# mother_card_07.net
KiCad netlist of a schematic drawn in EAGLE
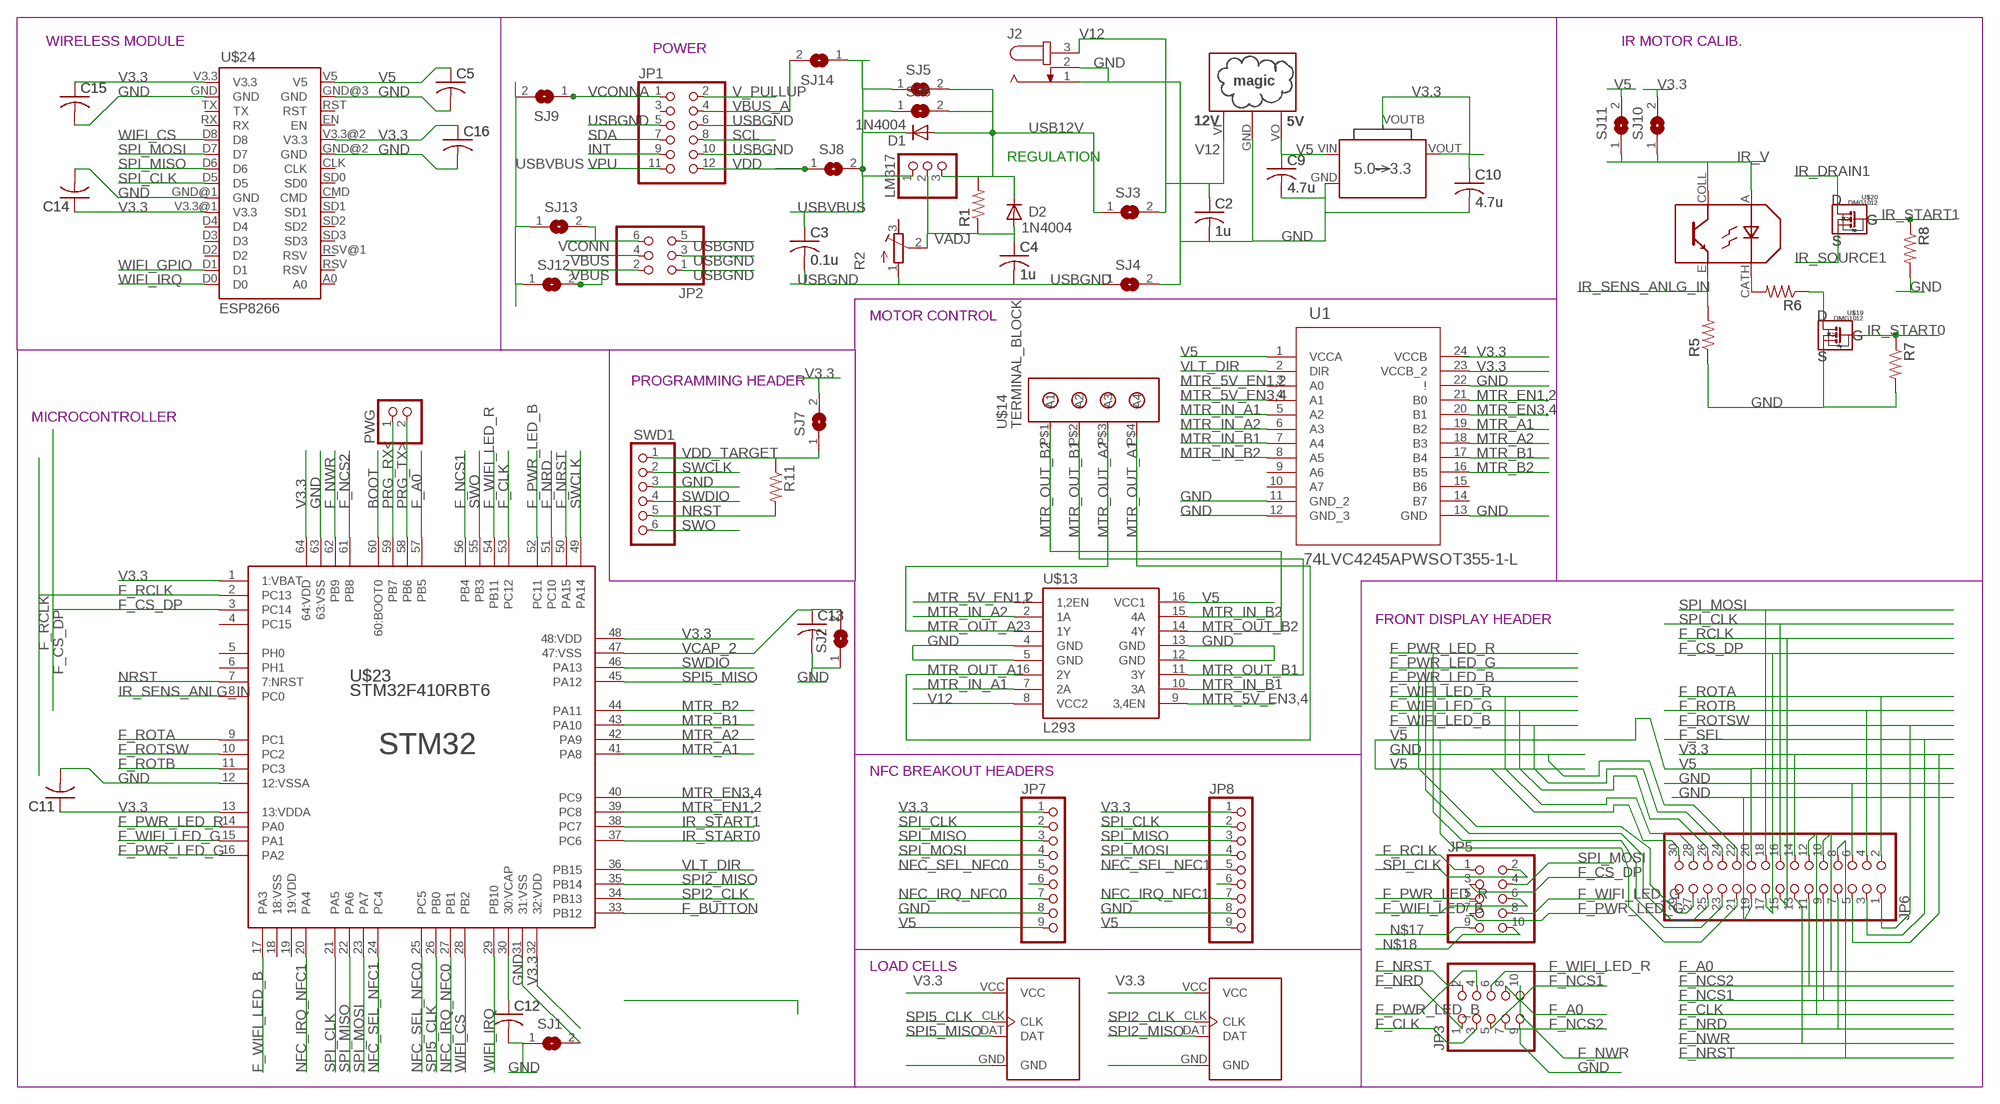
[diagram p0: schematic, sheet 1]

(export (version "E")
  (design (tool "Eeschema 10.0.6"))
  (components
    (comp (ref "C2")
      (value "1u")
      (footprint "eagle-import:C0805")
      (libsource (lib "eagle-import") (part "C-USC0805"))
    )
    (comp (ref "C3")
      (value "0.1u")
      (footprint "eagle-import:C0805")
      (libsource (lib "eagle-import") (part "C-USC0805"))
    )
    (comp (ref "C4")
      (value "1u")
      (footprint "eagle-import:C0805")
      (libsource (lib "eagle-import") (part "C-USC0805"))
    )
    (comp (ref "C5")
      (value "C-USC0805")
      (footprint "eagle-import:C0805")
      (libsource (lib "eagle-import") (part "C-USC0805"))
    )
    (comp (ref "C9")
      (value "4.7u")
      (footprint "eagle-import:C0805")
      (libsource (lib "eagle-import") (part "C-USC0805"))
    )
    (comp (ref "C10")
      (value "4.7u")
      (footprint "eagle-import:C0805")
      (libsource (lib "eagle-import") (part "C-USC0805"))
    )
    (comp (ref "C11")
      (value "C-USC0805")
      (footprint "eagle-import:C0805")
      (libsource (lib "eagle-import") (part "C-USC0805"))
    )
    (comp (ref "C12")
      (value "C-USC0805")
      (footprint "eagle-import:C0805")
      (libsource (lib "eagle-import") (part "C-USC0805"))
    )
    (comp (ref "C13")
      (value "C-USC0805")
      (footprint "eagle-import:C0805")
      (libsource (lib "eagle-import") (part "C-USC0805"))
    )
    (comp (ref "C14")
      (value "C-USC0805")
      (footprint "eagle-import:C0805")
      (libsource (lib "eagle-import") (part "C-USC0805"))
    )
    (comp (ref "C15")
      (value "C-USC0805")
      (footprint "eagle-import:C0805")
      (libsource (lib "eagle-import") (part "C-USC0805"))
    )
    (comp (ref "C16")
      (value "C-USC0805")
      (footprint "eagle-import:C0805")
      (libsource (lib "eagle-import") (part "C-USC0805"))
    )
    (comp (ref "D1")
      (value "1N4004")
      (footprint "eagle-import:DO41-10")
      (libsource (lib "eagle-import") (part "1N4004"))
    )
    (comp (ref "D2")
      (value "1N4004")
      (footprint "eagle-import:DO41-10")
      (libsource (lib "eagle-import") (part "1N4004"))
    )
    (comp (ref "J2")
      (value "JACK-PLUG0")
      (footprint "eagle-import:SPC4077")
      (libsource (lib "eagle-import") (part "JACK-PLUG0"))
    )
    (comp (ref "JP1")
      (value "PINHD-2X6")
      (footprint "eagle-import:2X06")
      (libsource (lib "eagle-import") (part "PINHD-2X6"))
    )
    (comp (ref "JP2")
      (value "PINHD-2X3")
      (footprint "eagle-import:2X03")
      (libsource (lib "eagle-import") (part "PINHD-2X3"))
    )
    (comp (ref "JP3")
      (value "PINHD-2X5")
      (footprint "eagle-import:2X05")
      (libsource (lib "eagle-import") (part "PINHD-2X5"))
    )
    (comp (ref "JP5")
      (value "PINHD-2X5")
      (footprint "eagle-import:2X05")
      (libsource (lib "eagle-import") (part "PINHD-2X5"))
    )
    (comp (ref "JP6")
      (value "PINHD-2X15/SOCK")
      (footprint "eagle-import:2X15_SOCK")
      (libsource (lib "eagle-import") (part "PINHD-2X15/SOCK"))
    )
    (comp (ref "JP7")
      (value "PINHD-1X9/90")
      (footprint "eagle-import:1X09_90")
      (libsource (lib "eagle-import") (part "PINHD-1X9/90"))
    )
    (comp (ref "JP8")
      (value "PINHD-1X9/90")
      (footprint "eagle-import:1X09_90")
      (libsource (lib "eagle-import") (part "PINHD-1X9/90"))
    )
    (comp (ref "LM317")
      (value "PINHD-1X3")
      (footprint "eagle-import:1X03")
      (libsource (lib "eagle-import") (part "PINHD-1X3"))
    )
    (comp (ref "PWG")
      (value "PINHD-1X2")
      (footprint "eagle-import:1X02")
      (libsource (lib "eagle-import") (part "PINHD-1X2"))
    )
    (comp (ref "R1")
      (value "R-US_R0805")
      (footprint "eagle-import:R0805")
      (libsource (lib "eagle-import") (part "seniorDesign_R-US_R0805"))
    )
    (comp (ref "R2")
      (value "R-TRIMM64W")
      (footprint "eagle-import:RTRIM64W")
      (libsource (lib "eagle-import") (part "R-TRIMM64W"))
    )
    (comp (ref "R5")
      (value "R-US_R0805")
      (footprint "eagle-import:R0805")
      (libsource (lib "eagle-import") (part "seniorDesign_R-US_R0805"))
    )
    (comp (ref "R6")
      (value "R-US_R0805")
      (footprint "eagle-import:R0805")
      (libsource (lib "eagle-import") (part "seniorDesign_R-US_R0805"))
    )
    (comp (ref "R7")
      (value "R-US_R0805")
      (footprint "eagle-import:R0805")
      (libsource (lib "eagle-import") (part "seniorDesign_R-US_R0805"))
    )
    (comp (ref "R8")
      (value "R-US_R0805")
      (footprint "eagle-import:R0805")
      (libsource (lib "eagle-import") (part "seniorDesign_R-US_R0805"))
    )
    (comp (ref "R11")
      (value "R-US_R0805")
      (footprint "eagle-import:R0805")
      (libsource (lib "eagle-import") (part "R-US_R0805"))
    )
    (comp (ref "SJ1") (value "SJ") (footprint "eagle-import:SJ") (libsource (lib "eagle-import") (part "SJ")))
    (comp (ref "SJ2") (value "SJ") (footprint "eagle-import:SJ") (libsource (lib "eagle-import") (part "SJ")))
    (comp (ref "SJ3") (value "SJ") (footprint "eagle-import:SJ") (libsource (lib "eagle-import") (part "SJ")))
    (comp (ref "SJ4") (value "SJ") (footprint "eagle-import:SJ") (libsource (lib "eagle-import") (part "SJ")))
    (comp (ref "SJ5") (value "SJ") (footprint "eagle-import:SJ") (libsource (lib "eagle-import") (part "SJ")))
    (comp (ref "SJ6") (value "SJ") (footprint "eagle-import:SJ") (libsource (lib "eagle-import") (part "SJ")))
    (comp (ref "SJ7") (value "SJ") (footprint "eagle-import:SJ") (libsource (lib "eagle-import") (part "SJ")))
    (comp (ref "SJ8") (value "SJ") (footprint "eagle-import:SJ") (libsource (lib "eagle-import") (part "SJ")))
    (comp (ref "SJ9") (value "SJ") (footprint "eagle-import:SJ") (libsource (lib "eagle-import") (part "SJ")))
    (comp (ref "SJ10")
      (value "SJ")
      (footprint "eagle-import:SJ")
      (libsource (lib "eagle-import") (part "SJ"))
    )
    (comp (ref "SJ11")
      (value "SJ")
      (footprint "eagle-import:SJ")
      (libsource (lib "eagle-import") (part "SJ"))
    )
    (comp (ref "SJ12")
      (value "SJ")
      (footprint "eagle-import:SJ")
      (libsource (lib "eagle-import") (part "SJ"))
    )
    (comp (ref "SJ13")
      (value "SJ")
      (footprint "eagle-import:SJ")
      (libsource (lib "eagle-import") (part "SJ"))
    )
    (comp (ref "SJ14")
      (value "SJ")
      (footprint "eagle-import:SJ")
      (libsource (lib "eagle-import") (part "SJ"))
    )
    (comp (ref "SWD1")
      (value "PINHD-1X6")
      (footprint "eagle-import:1X06")
      (libsource (lib "eagle-import") (part "PINHD-1X6"))
    )
    (comp (ref "U$13")
      (value "L293")
      (footprint "eagle-import:DIL16")
      (libsource (lib "eagle-import") (part "L293"))
    )
    (comp (ref "U$14")
      (value "TERMINAL_BLOCK")
      (footprint "eagle-import:1X4_BLOCK")
      (libsource (lib "eagle-import") (part "TERMINAL_BLOCK"))
    )
    (comp (ref "U$15")
      (value "AP2114H")
      (footprint "eagle-import:AP2114H")
      (libsource (lib "eagle-import") (part "AP2114H"))
    )
    (comp (ref "U$16")
      (value "OKI-78SR-W36")
      (footprint "eagle-import:SIP3")
      (libsource (lib "eagle-import") (part "OKI-78SR-W36"))
    )
    (comp (ref "U$18")
      (value "TCRT5000")
      (footprint "eagle-import:TCRT5000")
      (libsource (lib "eagle-import") (part "TCRT5000"))
    )
    (comp (ref "U$19")
      (value "DMG1012")
      (footprint "eagle-import:SOT323")
      (libsource (lib "eagle-import") (part "DMG1012"))
    )
    (comp (ref "U$20")
      (value "DMG1012")
      (footprint "eagle-import:SOT323")
      (libsource (lib "eagle-import") (part "DMG1012"))
    )
    (comp (ref "U$21")
      (value "HX711")
      (footprint "eagle-import:HX711")
      (libsource (lib "eagle-import") (part "HX711"))
    )
    (comp (ref "U$22")
      (value "HX711")
      (footprint "eagle-import:HX711")
      (libsource (lib "eagle-import") (part "HX711"))
    )
    (comp (ref "U$23")
      (value "STM32F410RBT6")
      (footprint "eagle-import:QFP50P1200X1200X160-64N")
      (libsource (lib "eagle-import") (part "STM32F410RBT6"))
    )
    (comp (ref "U$24")
      (value "ESP8266")
      (footprint "eagle-import:ESP8266")
      (libsource (lib "eagle-import") (part "ESP8266"))
    )
    (comp (ref "U1")
      (value "74LVC4245APWSOT355-1-L")
      (footprint "eagle-import:SOT355-1-L")
      (fields (field (name "MANUFACTURER_PART_NUMBER") "74LVC4245APW"))
      (libsource (lib "eagle-import") (part "74LVC4245APWSOT355-1-L"))
    )
  )
  (nets
    (net (code "1") (name "/BOOT") (class "Default")
      (node (ref "U$23") (pin "60") (pinfunction "60:BOOT0_60") (pintype "bidirectional"))
    )
    (net (code "2") (name "/F_A0") (class "Default")
      (node (ref "JP3") (pin "8") (pinfunction "8_8") (pintype "passive"))
      (node (ref "JP6") (pin "10") (pinfunction "10_10") (pintype "passive"))
      (node (ref "U$23") (pin "57") (pinfunction "PB5_57") (pintype "bidirectional"))
    )
    (net (code "3") (name "/F_BUTTON") (class "Default")
      (node (ref "U$23") (pin "33") (pinfunction "PB12_33") (pintype "bidirectional"))
    )
    (net (code "4") (name "/F_CLK") (class "Default")
      (node (ref "JP3") (pin "3") (pinfunction "3_3") (pintype "passive"))
      (node (ref "JP6") (pin "12") (pinfunction "12_12") (pintype "passive"))
      (node (ref "U$23") (pin "53") (pinfunction "PC12_53") (pintype "bidirectional"))
    )
    (net (code "5") (name "/F_CS_DP") (class "Default")
      (node (ref "JP5") (pin "3") (pinfunction "3_3") (pintype "passive"))
      (node (ref "JP6") (pin "17") (pinfunction "17_17") (pintype "passive"))
      (node (ref "U$23") (pin "3") (pinfunction "PC14_3") (pintype "bidirectional"))
    )
    (net (code "6") (name "/F_NCS1") (class "Default")
      (node (ref "JP3") (pin "5") (pinfunction "5_5") (pintype "passive"))
      (node (ref "JP6") (pin "9") (pinfunction "9_9") (pintype "passive"))
      (node (ref "U$23") (pin "56") (pinfunction "PB4_56") (pintype "bidirectional"))
    )
    (net (code "7") (name "/F_NCS2") (class "Default")
      (node (ref "JP3") (pin "7") (pinfunction "7_7") (pintype "passive"))
      (node (ref "JP6") (pin "11") (pinfunction "11_11") (pintype "passive"))
      (node (ref "U$23") (pin "61") (pinfunction "PB8_61") (pintype "bidirectional"))
    )
    (net (code "8") (name "/F_NRD") (class "Default")
      (node (ref "JP3") (pin "1") (pinfunction "1_1") (pintype "passive"))
      (node (ref "JP6") (pin "7") (pinfunction "7_7") (pintype "passive"))
      (node (ref "U$23") (pin "51") (pinfunction "PC10_51") (pintype "bidirectional"))
    )
    (net (code "9") (name "/F_NRST") (class "Default")
      (node (ref "JP3") (pin "2") (pinfunction "2_2") (pintype "passive"))
      (node (ref "JP6") (pin "8") (pinfunction "8_8") (pintype "passive"))
      (node (ref "U$23") (pin "50") (pinfunction "PA15_50") (pintype "bidirectional"))
    )
    (net (code "10") (name "/F_NWR") (class "Default")
      (node (ref "JP3") (pin "10") (pinfunction "10_10") (pintype "passive"))
      (node (ref "JP6") (pin "13") (pinfunction "13_13") (pintype "passive"))
      (node (ref "U$23") (pin "62") (pinfunction "PB9_62") (pintype "bidirectional"))
    )
    (net (code "11") (name "/F_PWR_LED_B") (class "Default")
      (node (ref "JP3") (pin "4") (pinfunction "4_4") (pintype "passive"))
      (node (ref "JP6") (pin "27") (pinfunction "27_27") (pintype "passive"))
      (node (ref "U$23") (pin "52") (pinfunction "PC11_52") (pintype "bidirectional"))
    )
    (net (code "12") (name "/F_PWR_LED_G") (class "Default")
      (node (ref "JP5") (pin "7") (pinfunction "7_7") (pintype "passive"))
      (node (ref "JP6") (pin "25") (pinfunction "25_25") (pintype "passive"))
      (node (ref "U$23") (pin "16") (pinfunction "PA2_16") (pintype "bidirectional"))
    )
    (net (code "13") (name "/F_PWR_LED_R") (class "Default")
      (node (ref "JP5") (pin "5") (pinfunction "5_5") (pintype "passive"))
      (node (ref "JP6") (pin "23") (pinfunction "23_23") (pintype "passive"))
      (node (ref "U$23") (pin "14") (pinfunction "PA0_14") (pintype "bidirectional"))
    )
    (net (code "14") (name "/F_RCLK") (class "Default")
      (node (ref "JP5") (pin "1") (pinfunction "1_1") (pintype "passive"))
      (node (ref "JP6") (pin "15") (pinfunction "15_15") (pintype "passive"))
      (node (ref "U$23") (pin "2") (pinfunction "PC13_2") (pintype "bidirectional"))
    )
    (net (code "15") (name "/F_ROTA") (class "Default")
      (node (ref "JP6") (pin "2") (pinfunction "2_2") (pintype "passive"))
      (node (ref "U$23") (pin "9") (pinfunction "PC1_9") (pintype "bidirectional"))
    )
    (net (code "16") (name "/F_ROTB") (class "Default")
      (node (ref "JP6") (pin "4") (pinfunction "4_4") (pintype "passive"))
      (node (ref "U$23") (pin "11") (pinfunction "PC3_11") (pintype "bidirectional"))
    )
    (net (code "17") (name "/F_ROTSW") (class "Default")
      (node (ref "JP6") (pin "1") (pinfunction "1_1") (pintype "passive"))
      (node (ref "U$23") (pin "10") (pinfunction "PC2_10") (pintype "bidirectional"))
    )
    (net (code "18") (name "/F_SEL") (class "Default")
      (node (ref "JP6") (pin "3") (pinfunction "3_3") (pintype "passive"))
    )
    (net (code "19") (name "/F_WIFI_LED_B") (class "Default")
      (node (ref "JP5") (pin "6") (pinfunction "6_6") (pintype "passive"))
      (node (ref "JP6") (pin "24") (pinfunction "24_24") (pintype "passive"))
      (node (ref "U$23") (pin "17") (pinfunction "PA3_17") (pintype "bidirectional"))
    )
    (net (code "20") (name "/F_WIFI_LED_G") (class "Default")
      (node (ref "JP5") (pin "8") (pinfunction "8_8") (pintype "passive"))
      (node (ref "JP6") (pin "26") (pinfunction "26_26") (pintype "passive"))
      (node (ref "U$23") (pin "15") (pinfunction "PA1_15") (pintype "bidirectional"))
    )
    (net (code "21") (name "/F_WIFI_LED_R") (class "Default")
      (node (ref "JP3") (pin "6") (pinfunction "6_6") (pintype "passive"))
      (node (ref "JP6") (pin "28") (pinfunction "28_28") (pintype "passive"))
      (node (ref "U$23") (pin "54") (pinfunction "PB11_54") (pintype "bidirectional"))
    )
    (net (code "22") (name "/GND") (class "Default")
      (node (ref "C10") (pin "2") (pinfunction "2_2") (pintype "passive"))
      (node (ref "C11") (pin "2") (pinfunction "2_2") (pintype "passive"))
      (node (ref "C12") (pin "2") (pinfunction "2_2") (pintype "passive"))
      (node (ref "C13") (pin "2") (pinfunction "2_2") (pintype "passive"))
      (node (ref "C14") (pin "2") (pinfunction "2_2") (pintype "passive"))
      (node (ref "C15") (pin "2") (pinfunction "2_2") (pintype "passive"))
      (node (ref "C16") (pin "2") (pinfunction "2_2") (pintype "passive"))
      (node (ref "C2") (pin "2") (pinfunction "2_2") (pintype "passive"))
      (node (ref "C5") (pin "2") (pinfunction "2_2") (pintype "passive"))
      (node (ref "C9") (pin "2") (pinfunction "2_2") (pintype "passive"))
      (node (ref "J2") (pin "1") (pinfunction "1_1") (pintype "passive"))
      (node (ref "J2") (pin "2") (pinfunction "2_2") (pintype "passive"))
      (node (ref "JP3") (pin "9") (pinfunction "9_9") (pintype "passive"))
      (node (ref "JP6") (pin "19") (pinfunction "19_19") (pintype "passive"))
      (node (ref "JP6") (pin "22") (pinfunction "22_22") (pintype "passive"))
      (node (ref "JP6") (pin "6") (pinfunction "6_6") (pintype "passive"))
      (node (ref "JP7") (pin "8") (pinfunction "8_8") (pintype "passive"))
      (node (ref "JP8") (pin "8") (pinfunction "8_8") (pintype "passive"))
      (node (ref "R5") (pin "1") (pinfunction "1_1") (pintype "passive"))
      (node (ref "R7") (pin "2") (pinfunction "2_2") (pintype "passive"))
      (node (ref "R8") (pin "2") (pinfunction "2_2") (pintype "passive"))
      (node (ref "SJ1") (pin "1") (pinfunction "1_1") (pintype "passive"))
      (node (ref "SJ1") (pin "2") (pinfunction "2_2") (pintype "passive"))
      (node (ref "SJ2") (pin "1") (pinfunction "1_1") (pintype "passive"))
      (node (ref "SJ4") (pin "2") (pinfunction "2_2") (pintype "passive"))
      (node (ref "SWD1") (pin "3") (pinfunction "3_3") (pintype "passive"))
      (node (ref "U$13") (pin "12") (pinfunction "GND_12") (pintype "bidirectional"))
      (node (ref "U$13") (pin "13") (pinfunction "GND_13") (pintype "bidirectional"))
      (node (ref "U$13") (pin "4") (pinfunction "GND_4") (pintype "bidirectional"))
      (node (ref "U$13") (pin "5") (pinfunction "GND_5") (pintype "bidirectional"))
      (node (ref "U$15") (pin "GND") (pinfunction "GND_GND") (pintype "power_in"))
      (node (ref "U$16") (pin "GND") (pinfunction "P$2_GND") (pintype "power_in"))
      (node (ref "U$19") (pin "S") (pinfunction "S_S") (pintype "bidirectional"))
      (node (ref "U$21") (pin "GND") (pinfunction "GND_GND") (pintype "power_in"))
      (node (ref "U$22") (pin "GND") (pinfunction "GND_GND") (pintype "power_in"))
      (node (ref "U$23") (pin "12") (pinfunction "12:VSSA_12") (pintype "bidirectional"))
      (node (ref "U$23") (pin "31") (pinfunction "31:VSS_31") (pintype "bidirectional"))
      (node (ref "U$23") (pin "63") (pinfunction "63:VSS_63") (pintype "bidirectional"))
      (node (ref "U$24") (pin "GND") (pinfunction "GND_GND") (pintype "bidirectional"))
      (node (ref "U$24") (pin "GND@1") (pinfunction "GND_GND@1") (pintype "bidirectional"))
      (node (ref "U$24") (pin "GND@2") (pinfunction "GND_GND@2") (pintype "bidirectional"))
      (node (ref "U$24") (pin "GND@3") (pinfunction "GND_GND@3") (pintype "bidirectional"))
      (node (ref "U1") (pin "11") (pinfunction "GND_2_11") (pintype "power_in"))
      (node (ref "U1") (pin "12") (pinfunction "GND_3_12") (pintype "power_in"))
      (node (ref "U1") (pin "13") (pinfunction "GND_13") (pintype "power_in"))
      (node (ref "U1") (pin "22") (pinfunction "~_22") (pintype "input"))
    )
    (net (code "23") (name "/INT") (class "Default")
      (node (ref "JP1") (pin "9") (pinfunction "9_9") (pintype "passive"))
    )
    (net (code "24") (name "/IR_DRAIN1") (class "Default")
      (node (ref "U$20") (pin "D") (pinfunction "D_D") (pintype "bidirectional"))
    )
    (net (code "25") (name "/IR_SENS_ANLG_IN") (class "Default")
      (node (ref "R5") (pin "2") (pinfunction "2_2") (pintype "passive"))
      (node (ref "U$18") (pin "E") (pinfunction "E_E") (pintype "bidirectional"))
      (node (ref "U$23") (pin "8") (pinfunction "PC0_8") (pintype "bidirectional"))
    )
    (net (code "26") (name "/IR_SOURCE1") (class "Default")
      (node (ref "U$20") (pin "S") (pinfunction "S_S") (pintype "bidirectional"))
    )
    (net (code "27") (name "/IR_START0") (class "Default")
      (node (ref "R7") (pin "1") (pinfunction "1_1") (pintype "passive"))
      (node (ref "U$19") (pin "G") (pinfunction "G_G") (pintype "bidirectional"))
      (node (ref "U$23") (pin "37") (pinfunction "PC6_37") (pintype "bidirectional"))
    )
    (net (code "28") (name "/IR_START1") (class "Default")
      (node (ref "R8") (pin "1") (pinfunction "1_1") (pintype "passive"))
      (node (ref "U$20") (pin "G") (pinfunction "G_G") (pintype "bidirectional"))
      (node (ref "U$23") (pin "38") (pinfunction "PC7_38") (pintype "bidirectional"))
    )
    (net (code "29") (name "/IR_V") (class "Default")
      (node (ref "SJ10") (pin "1") (pinfunction "1_1") (pintype "passive"))
      (node (ref "SJ11") (pin "1") (pinfunction "1_1") (pintype "passive"))
      (node (ref "U$18") (pin "A") (pinfunction "A_A") (pintype "bidirectional"))
      (node (ref "U$18") (pin "COLL") (pinfunction "COLL_COLL") (pintype "bidirectional"))
    )
    (net (code "30") (name "/MTR_5V_EN1,2") (class "Default")
      (node (ref "U$13") (pin "1") (pinfunction "1,2EN_1") (pintype "bidirectional"))
      (node (ref "U1") (pin "3") (pinfunction "A0_3") (pintype "bidirectional"))
    )
    (net (code "31") (name "/MTR_5V_EN3,4") (class "Default")
      (node (ref "U$13") (pin "9") (pinfunction "3,4EN_9") (pintype "bidirectional"))
      (node (ref "U1") (pin "4") (pinfunction "A1_4") (pintype "bidirectional"))
    )
    (net (code "32") (name "/MTR_A1") (class "Default")
      (node (ref "U$23") (pin "41") (pinfunction "PA8_41") (pintype "bidirectional"))
      (node (ref "U1") (pin "19") (pinfunction "B2_19") (pintype "bidirectional"))
    )
    (net (code "33") (name "/MTR_A2") (class "Default")
      (node (ref "U$23") (pin "42") (pinfunction "PA9_42") (pintype "bidirectional"))
      (node (ref "U1") (pin "18") (pinfunction "B3_18") (pintype "bidirectional"))
    )
    (net (code "34") (name "/MTR_B1") (class "Default")
      (node (ref "U$23") (pin "43") (pinfunction "PA10_43") (pintype "bidirectional"))
      (node (ref "U1") (pin "17") (pinfunction "B4_17") (pintype "bidirectional"))
    )
    (net (code "35") (name "/MTR_B2") (class "Default")
      (node (ref "U$23") (pin "44") (pinfunction "PA11_44") (pintype "bidirectional"))
      (node (ref "U1") (pin "16") (pinfunction "B5_16") (pintype "bidirectional"))
    )
    (net (code "36") (name "/MTR_EN1,2") (class "Default")
      (node (ref "U$23") (pin "39") (pinfunction "PC8_39") (pintype "bidirectional"))
      (node (ref "U1") (pin "21") (pinfunction "B0_21") (pintype "bidirectional"))
    )
    (net (code "37") (name "/MTR_EN3,4") (class "Default")
      (node (ref "U$23") (pin "40") (pinfunction "PC9_40") (pintype "bidirectional"))
      (node (ref "U1") (pin "20") (pinfunction "B1_20") (pintype "bidirectional"))
    )
    (net (code "38") (name "/MTR_IN_A1") (class "Default")
      (node (ref "U$13") (pin "7") (pinfunction "2A_7") (pintype "bidirectional"))
      (node (ref "U1") (pin "5") (pinfunction "A2_5") (pintype "bidirectional"))
    )
    (net (code "39") (name "/MTR_IN_A2") (class "Default")
      (node (ref "U$13") (pin "2") (pinfunction "1A_2") (pintype "bidirectional"))
      (node (ref "U1") (pin "6") (pinfunction "A3_6") (pintype "bidirectional"))
    )
    (net (code "40") (name "/MTR_IN_B1") (class "Default")
      (node (ref "U$13") (pin "10") (pinfunction "3A_10") (pintype "bidirectional"))
      (node (ref "U1") (pin "7") (pinfunction "A4_7") (pintype "bidirectional"))
    )
    (net (code "41") (name "/MTR_IN_B2") (class "Default")
      (node (ref "U$13") (pin "15") (pinfunction "4A_15") (pintype "bidirectional"))
      (node (ref "U1") (pin "8") (pinfunction "A5_8") (pintype "bidirectional"))
    )
    (net (code "42") (name "/MTR_OUT_A1") (class "Default")
      (node (ref "U$13") (pin "6") (pinfunction "2Y_6") (pintype "bidirectional"))
      (node (ref "U$14") (pin "P$4") (pinfunction "A4_P$4") (pintype "bidirectional"))
    )
    (net (code "43") (name "/MTR_OUT_A2") (class "Default")
      (node (ref "U$13") (pin "3") (pinfunction "1Y_3") (pintype "bidirectional"))
      (node (ref "U$14") (pin "P$3") (pinfunction "A3_P$3") (pintype "bidirectional"))
    )
    (net (code "44") (name "/MTR_OUT_B1") (class "Default")
      (node (ref "U$13") (pin "11") (pinfunction "3Y_11") (pintype "bidirectional"))
      (node (ref "U$14") (pin "P$2") (pinfunction "A2_P$2") (pintype "bidirectional"))
    )
    (net (code "45") (name "/MTR_OUT_B2") (class "Default")
      (node (ref "U$13") (pin "14") (pinfunction "4Y_14") (pintype "bidirectional"))
      (node (ref "U$14") (pin "P$1") (pinfunction "A1_P$1") (pintype "bidirectional"))
    )
    (net (code "46") (name "/N$17") (class "Default")
      (node (ref "JP5") (pin "9") (pinfunction "9_9") (pintype "passive"))
    )
    (net (code "47") (name "/N$18") (class "Default")
      (node (ref "JP5") (pin "10") (pinfunction "10_10") (pintype "passive"))
    )
    (net (code "48") (name "/NFC_IRQ_NFC0") (class "Default")
      (node (ref "JP7") (pin "7") (pinfunction "7_7") (pintype "passive"))
      (node (ref "U$23") (pin "27") (pinfunction "PB1_27") (pintype "bidirectional"))
    )
    (net (code "49") (name "/NFC_IRQ_NFC1") (class "Default")
      (node (ref "JP8") (pin "7") (pinfunction "7_7") (pintype "passive"))
      (node (ref "U$23") (pin "20") (pinfunction "PA4_20") (pintype "bidirectional"))
    )
    (net (code "50") (name "/NFC_SEL_NFC0") (class "Default")
      (node (ref "JP7") (pin "5") (pinfunction "5_5") (pintype "passive"))
      (node (ref "U$23") (pin "25") (pinfunction "PC5_25") (pintype "bidirectional"))
    )
    (net (code "51") (name "/NFC_SEL_NFC1") (class "Default")
      (node (ref "JP8") (pin "5") (pinfunction "5_5") (pintype "passive"))
      (node (ref "U$23") (pin "24") (pinfunction "PC4_24") (pintype "bidirectional"))
    )
    (net (code "52") (name "/NRST") (class "Default")
      (node (ref "R11") (pin "2") (pinfunction "2_2") (pintype "passive"))
      (node (ref "SWD1") (pin "5") (pinfunction "5_5") (pintype "passive"))
      (node (ref "U$23") (pin "7") (pinfunction "7:NRST_7") (pintype "bidirectional"))
    )
    (net (code "53") (name "/PRG_RX<") (class "Default")
      (node (ref "PWG") (pin "1") (pinfunction "1_1") (pintype "passive"))
      (node (ref "U$23") (pin "59") (pinfunction "PB7_59") (pintype "bidirectional"))
    )
    (net (code "54") (name "/PRG_TX>") (class "Default")
      (node (ref "PWG") (pin "2") (pinfunction "2_2") (pintype "passive"))
      (node (ref "U$23") (pin "58") (pinfunction "PB6_58") (pintype "bidirectional"))
    )
    (net (code "55") (name "/SCL") (class "Default")
      (node (ref "JP1") (pin "8") (pinfunction "8_8") (pintype "passive"))
    )
    (net (code "56") (name "/SDA") (class "Default")
      (node (ref "JP1") (pin "7") (pinfunction "7_7") (pintype "passive"))
    )
    (net (code "57") (name "/SPI2_CLK") (class "Default")
      (node (ref "U$22") (pin "CLK") (pinfunction "CLK_CLK") (pintype "bidirectional"))
      (node (ref "U$23") (pin "34") (pinfunction "PB13_34") (pintype "bidirectional"))
    )
    (net (code "58") (name "/SPI2_MISO") (class "Default")
      (node (ref "U$22") (pin "DAT") (pinfunction "DAT_DAT") (pintype "bidirectional"))
      (node (ref "U$23") (pin "35") (pinfunction "PB14_35") (pintype "bidirectional"))
    )
    (net (code "59") (name "/SPI5_CLK") (class "Default")
      (node (ref "U$21") (pin "CLK") (pinfunction "CLK_CLK") (pintype "bidirectional"))
      (node (ref "U$23") (pin "26") (pinfunction "PB0_26") (pintype "bidirectional"))
    )
    (net (code "60") (name "/SPI5_MISO") (class "Default")
      (node (ref "U$21") (pin "DAT") (pinfunction "DAT_DAT") (pintype "bidirectional"))
      (node (ref "U$23") (pin "45") (pinfunction "PA12_45") (pintype "bidirectional"))
    )
    (net (code "61") (name "/SPI_CLK") (class "Default")
      (node (ref "JP5") (pin "2") (pinfunction "2_2") (pintype "passive"))
      (node (ref "JP6") (pin "16") (pinfunction "16_16") (pintype "passive"))
      (node (ref "JP7") (pin "2") (pinfunction "2_2") (pintype "passive"))
      (node (ref "JP8") (pin "2") (pinfunction "2_2") (pintype "passive"))
      (node (ref "U$23") (pin "21") (pinfunction "PA5_21") (pintype "bidirectional"))
      (node (ref "U$24") (pin "D5") (pinfunction "D5_D5") (pintype "bidirectional"))
    )
    (net (code "62") (name "/SPI_MISO") (class "Default")
      (node (ref "JP7") (pin "3") (pinfunction "3_3") (pintype "passive"))
      (node (ref "JP8") (pin "3") (pinfunction "3_3") (pintype "passive"))
      (node (ref "U$23") (pin "22") (pinfunction "PA6_22") (pintype "bidirectional"))
      (node (ref "U$24") (pin "D6") (pinfunction "D6_D6") (pintype "bidirectional"))
    )
    (net (code "63") (name "/SPI_MOSI") (class "Default")
      (node (ref "JP5") (pin "4") (pinfunction "4_4") (pintype "passive"))
      (node (ref "JP6") (pin "18") (pinfunction "18_18") (pintype "passive"))
      (node (ref "JP7") (pin "4") (pinfunction "4_4") (pintype "passive"))
      (node (ref "JP8") (pin "4") (pinfunction "4_4") (pintype "passive"))
      (node (ref "U$23") (pin "23") (pinfunction "PA7_23") (pintype "bidirectional"))
      (node (ref "U$24") (pin "D7") (pinfunction "D7_D7") (pintype "bidirectional"))
    )
    (net (code "64") (name "/SWCLK") (class "Default")
      (node (ref "SWD1") (pin "2") (pinfunction "2_2") (pintype "passive"))
      (node (ref "U$23") (pin "49") (pinfunction "PA14_49") (pintype "bidirectional"))
    )
    (net (code "65") (name "/SWDIO") (class "Default")
      (node (ref "SWD1") (pin "4") (pinfunction "4_4") (pintype "passive"))
      (node (ref "U$23") (pin "46") (pinfunction "PA13_46") (pintype "bidirectional"))
    )
    (net (code "66") (name "/SWO") (class "Default")
      (node (ref "SWD1") (pin "6") (pinfunction "6_6") (pintype "passive"))
      (node (ref "U$23") (pin "55") (pinfunction "PB3_55") (pintype "bidirectional"))
    )
    (net (code "67") (name "/USB12V") (class "Default")
      (node (ref "D1") (pin "A") (pinfunction "A_A") (pintype "passive"))
      (node (ref "D2") (pin "C") (pinfunction "C_C") (pintype "passive"))
      (node (ref "LM317") (pin "3") (pinfunction "3_3") (pintype "passive"))
      (node (ref "R1") (pin "2") (pinfunction "2_2") (pintype "passive"))
      (node (ref "SJ3") (pin "1") (pinfunction "1_1") (pintype "passive"))
      (node (ref "SJ5") (pin "2") (pinfunction "2_2") (pintype "passive"))
      (node (ref "SJ6") (pin "2") (pinfunction "2_2") (pintype "passive"))
    )
    (net (code "68") (name "/USBGND") (class "Default")
      (node (ref "C3") (pin "2") (pinfunction "2_2") (pintype "passive"))
      (node (ref "C4") (pin "2") (pinfunction "2_2") (pintype "passive"))
      (node (ref "JP1") (pin "10") (pinfunction "10_10") (pintype "passive"))
      (node (ref "JP1") (pin "5") (pinfunction "5_5") (pintype "passive"))
      (node (ref "JP1") (pin "6") (pinfunction "6_6") (pintype "passive"))
      (node (ref "JP2") (pin "1") (pinfunction "1_1") (pintype "passive"))
      (node (ref "JP2") (pin "3") (pinfunction "3_3") (pintype "passive"))
      (node (ref "JP2") (pin "5") (pinfunction "5_5") (pintype "passive"))
      (node (ref "R2") (pin "1") (pinfunction "A_1") (pintype "passive"))
      (node (ref "SJ4") (pin "1") (pinfunction "1_1") (pintype "passive"))
    )
    (net (code "69") (name "/USBVBUS") (class "Default")
      (node (ref "C3") (pin "1") (pinfunction "1_1") (pintype "passive"))
      (node (ref "D1") (pin "C") (pinfunction "C_C") (pintype "passive"))
      (node (ref "LM317") (pin "1") (pinfunction "1_1") (pintype "passive"))
      (node (ref "SJ12") (pin "1") (pinfunction "1_1") (pintype "passive"))
      (node (ref "SJ13") (pin "1") (pinfunction "1_1") (pintype "passive"))
      (node (ref "SJ14") (pin "1") (pinfunction "1_1") (pintype "passive"))
      (node (ref "SJ5") (pin "1") (pinfunction "1_1") (pintype "passive"))
      (node (ref "SJ6") (pin "1") (pinfunction "1_1") (pintype "passive"))
      (node (ref "SJ8") (pin "2") (pinfunction "2_2") (pintype "passive"))
      (node (ref "SJ9") (pin "2") (pinfunction "2_2") (pintype "passive"))
    )
    (net (code "70") (name "/V3.3") (class "Default")
      (node (ref "C10") (pin "1") (pinfunction "1_1") (pintype "passive"))
      (node (ref "C11") (pin "1") (pinfunction "1_1") (pintype "passive"))
      (node (ref "C14") (pin "1") (pinfunction "1_1") (pintype "passive"))
      (node (ref "C15") (pin "1") (pinfunction "1_1") (pintype "passive"))
      (node (ref "C16") (pin "1") (pinfunction "1_1") (pintype "passive"))
      (node (ref "JP6") (pin "14") (pinfunction "14_14") (pintype "passive"))
      (node (ref "JP6") (pin "5") (pinfunction "5_5") (pintype "passive"))
      (node (ref "JP7") (pin "1") (pinfunction "1_1") (pintype "passive"))
      (node (ref "JP8") (pin "1") (pinfunction "1_1") (pintype "passive"))
      (node (ref "SJ10") (pin "2") (pinfunction "2_2") (pintype "passive"))
      (node (ref "SJ7") (pin "2") (pinfunction "2_2") (pintype "passive"))
      (node (ref "U$15") (pin "VOUT") (pinfunction "VO_VOUT") (pintype "output"))
      (node (ref "U$15") (pin "VOUTB") (pinfunction "BODY_VOUTB") (pintype "open_collector"))
      (node (ref "U$21") (pin "VCC") (pinfunction "VCC_VCC") (pintype "power_in"))
      (node (ref "U$22") (pin "VCC") (pinfunction "VCC_VCC") (pintype "power_in"))
      (node (ref "U$23") (pin "1") (pinfunction "1:VBAT_1") (pintype "bidirectional"))
      (node (ref "U$23") (pin "13") (pinfunction "13:VDDA_13") (pintype "bidirectional"))
      (node (ref "U$23") (pin "32") (pinfunction "32:VDD_32") (pintype "bidirectional"))
      (node (ref "U$23") (pin "48") (pinfunction "48:VDD_48") (pintype "bidirectional"))
      (node (ref "U$23") (pin "64") (pinfunction "64:VDD_64") (pintype "bidirectional"))
      (node (ref "U$24") (pin "V3.3") (pinfunction "V3.3_V3.3") (pintype "bidirectional"))
      (node (ref "U$24") (pin "V3.3@1") (pinfunction "V3.3_V3.3@1") (pintype "bidirectional"))
      (node (ref "U$24") (pin "V3.3@2") (pinfunction "V3.3_V3.3@2") (pintype "bidirectional"))
      (node (ref "U1") (pin "23") (pinfunction "VCCB_2_23") (pintype "power_in"))
      (node (ref "U1") (pin "24") (pinfunction "VCCB_24") (pintype "power_in"))
    )
    (net (code "71") (name "/V5") (class "Default")
      (node (ref "C5") (pin "1") (pinfunction "1_1") (pintype "passive"))
      (node (ref "C9") (pin "1") (pinfunction "1_1") (pintype "passive"))
      (node (ref "JP6") (pin "20") (pinfunction "20_20") (pintype "passive"))
      (node (ref "JP6") (pin "21") (pinfunction "21_21") (pintype "passive"))
      (node (ref "JP6") (pin "30") (pinfunction "30_30") (pintype "passive"))
      (node (ref "JP7") (pin "9") (pinfunction "9_9") (pintype "passive"))
      (node (ref "JP8") (pin "9") (pinfunction "9_9") (pintype "passive"))
      (node (ref "SJ11") (pin "2") (pinfunction "2_2") (pintype "passive"))
      (node (ref "U$13") (pin "16") (pinfunction "VCC1_16") (pintype "bidirectional"))
      (node (ref "U$15") (pin "VIN") (pinfunction "VI_VIN") (pintype "input"))
      (node (ref "U$16") (pin "VO") (pinfunction "P$3_VO") (pintype "output"))
      (node (ref "U$24") (pin "V5") (pinfunction "V5_V5") (pintype "bidirectional"))
      (node (ref "U1") (pin "1") (pinfunction "VCCA_1") (pintype "power_in"))
    )
    (net (code "72") (name "/V12") (class "Default")
      (node (ref "C2") (pin "1") (pinfunction "1_1") (pintype "passive"))
      (node (ref "J2") (pin "3") (pinfunction "3_3") (pintype "passive"))
      (node (ref "SJ3") (pin "2") (pinfunction "2_2") (pintype "passive"))
      (node (ref "U$13") (pin "8") (pinfunction "VCC2_8") (pintype "bidirectional"))
      (node (ref "U$16") (pin "VI") (pinfunction "P$1_VI") (pintype "input"))
    )
    (net (code "73") (name "/VADJ") (class "Default")
      (node (ref "C4") (pin "1") (pinfunction "1_1") (pintype "passive"))
      (node (ref "D2") (pin "A") (pinfunction "A_A") (pintype "passive"))
      (node (ref "LM317") (pin "2") (pinfunction "2_2") (pintype "passive"))
      (node (ref "R1") (pin "1") (pinfunction "1_1") (pintype "passive"))
      (node (ref "R2") (pin "2") (pinfunction "S_2") (pintype "passive"))
    )
    (net (code "74") (name "/VBUS") (class "Default")
      (node (ref "JP2") (pin "2") (pinfunction "2_2") (pintype "passive"))
      (node (ref "JP2") (pin "4") (pinfunction "4_4") (pintype "passive"))
      (node (ref "SJ12") (pin "2") (pinfunction "2_2") (pintype "passive"))
    )
    (net (code "75") (name "/VBUS_A") (class "Default")
      (node (ref "JP1") (pin "4") (pinfunction "4_4") (pintype "passive"))
      (node (ref "SJ14") (pin "2") (pinfunction "2_2") (pintype "passive"))
    )
    (net (code "76") (name "/VCAP_2") (class "Default")
      (node (ref "C13") (pin "1") (pinfunction "1_1") (pintype "passive"))
      (node (ref "SJ2") (pin "2") (pinfunction "2_2") (pintype "passive"))
      (node (ref "U$23") (pin "47") (pinfunction "47:VSS_47") (pintype "bidirectional"))
    )
    (net (code "77") (name "/VCONN") (class "Default")
      (node (ref "JP2") (pin "6") (pinfunction "6_6") (pintype "passive"))
      (node (ref "SJ13") (pin "2") (pinfunction "2_2") (pintype "passive"))
    )
    (net (code "78") (name "/VCONNA") (class "Default")
      (node (ref "JP1") (pin "1") (pinfunction "1_1") (pintype "passive"))
      (node (ref "SJ9") (pin "1") (pinfunction "1_1") (pintype "passive"))
    )
    (net (code "79") (name "/VDD") (class "Default")
      (node (ref "JP1") (pin "12") (pinfunction "12_12") (pintype "passive"))
      (node (ref "SJ8") (pin "1") (pinfunction "1_1") (pintype "passive"))
    )
    (net (code "80") (name "/VDD_TARGET") (class "Default")
      (node (ref "R11") (pin "1") (pinfunction "1_1") (pintype "passive"))
      (node (ref "SJ7") (pin "1") (pinfunction "1_1") (pintype "passive"))
      (node (ref "SWD1") (pin "1") (pinfunction "1_1") (pintype "passive"))
    )
    (net (code "81") (name "/VLT_DIR") (class "Default")
      (node (ref "U$23") (pin "36") (pinfunction "PB15_36") (pintype "bidirectional"))
      (node (ref "U1") (pin "2") (pinfunction "DIR_2") (pintype "input"))
    )
    (net (code "82") (name "/VPU") (class "Default")
      (node (ref "JP1") (pin "11") (pinfunction "11_11") (pintype "passive"))
    )
    (net (code "83") (name "/V_PULLUP") (class "Default")
      (node (ref "JP1") (pin "2") (pinfunction "2_2") (pintype "passive"))
    )
    (net (code "84") (name "/WIFI_CS") (class "Default")
      (node (ref "U$23") (pin "28") (pinfunction "PB2_28") (pintype "bidirectional"))
      (node (ref "U$24") (pin "D8") (pinfunction "D8_D8") (pintype "bidirectional"))
    )
    (net (code "85") (name "/WIFI_GPIO") (class "Default")
      (node (ref "U$24") (pin "D1") (pinfunction "D1_D1") (pintype "bidirectional"))
    )
    (net (code "86") (name "/WIFI_IRQ") (class "Default")
      (node (ref "U$23") (pin "29") (pinfunction "PB10_29") (pintype "bidirectional"))
      (node (ref "U$24") (pin "D0") (pinfunction "D0_D0") (pintype "bidirectional"))
    )
    (net (code "87") (name "Net-(R6-Pad1)") (class "Default")
      (node (ref "R6") (pin "1") (pinfunction "1_1") (pintype "passive"))
      (node (ref "U$19") (pin "D") (pinfunction "D_D") (pintype "bidirectional"))
    )
    (net (code "88") (name "Net-(R6-Pad2)") (class "Default")
      (node (ref "R6") (pin "2") (pinfunction "2_2") (pintype "passive"))
      (node (ref "U$18") (pin "CATH") (pinfunction "CATH_CATH") (pintype "bidirectional"))
    )
    (net (code "89") (name "Net-(U$23-30:VCAP)") (class "Default")
      (node (ref "C12") (pin "1") (pinfunction "1_1") (pintype "passive"))
      (node (ref "U$23") (pin "30") (pinfunction "30:VCAP_30") (pintype "bidirectional"))
    )
    (net (code "90") (name "unconnected-(JP1-Pad3)") (class "Default")
      (node (ref "JP1") (pin "3") (pinfunction "3_3") (pintype "passive"))
    )
    (net (code "91") (name "unconnected-(JP6-Pad29)") (class "Default")
      (node (ref "JP6") (pin "29") (pinfunction "29_29") (pintype "passive"))
    )
    (net (code "92") (name "unconnected-(JP7-Pad6)") (class "Default")
      (node (ref "JP7") (pin "6") (pinfunction "6_6") (pintype "passive"))
    )
    (net (code "93") (name "unconnected-(JP8-Pad6)") (class "Default")
      (node (ref "JP8") (pin "6") (pinfunction "6_6") (pintype "passive"))
    )
    (net (code "94") (name "unconnected-(R2-E-Pad3)") (class "Default")
      (node (ref "R2") (pin "3") (pinfunction "E_3") (pintype "passive"))
    )
    (net (code "95") (name "unconnected-(U$23-18:VSS-Pad18)") (class "Default")
      (node (ref "U$23") (pin "18") (pinfunction "18:VSS_18") (pintype "bidirectional"))
    )
    (net (code "96") (name "unconnected-(U$23-19:VDD-Pad19)") (class "Default")
      (node (ref "U$23") (pin "19") (pinfunction "19:VDD_19") (pintype "bidirectional"))
    )
    (net (code "97") (name "unconnected-(U$23-PC15-Pad4)") (class "Default")
      (node (ref "U$23") (pin "4") (pinfunction "PC15_4") (pintype "bidirectional"))
    )
    (net (code "98") (name "unconnected-(U$23-PH0-Pad5)") (class "Default")
      (node (ref "U$23") (pin "5") (pinfunction "PH0_5") (pintype "bidirectional"))
    )
    (net (code "99") (name "unconnected-(U$23-PH1-Pad6)") (class "Default")
      (node (ref "U$23") (pin "6") (pinfunction "PH1_6") (pintype "bidirectional"))
    )
    (net (code "100") (name "unconnected-(U$24-PadA0)") (class "Default")
      (node (ref "U$24") (pin "A0") (pinfunction "A0_A0") (pintype "bidirectional"))
    )
    (net (code "101") (name "unconnected-(U$24-PadCLK)") (class "Default")
      (node (ref "U$24") (pin "CLK") (pinfunction "CLK_CLK") (pintype "bidirectional"))
    )
    (net (code "102") (name "unconnected-(U$24-PadCMD)") (class "Default")
      (node (ref "U$24") (pin "CMD") (pinfunction "CMD_CMD") (pintype "bidirectional"))
    )
    (net (code "103") (name "unconnected-(U$24-PadD2)") (class "Default")
      (node (ref "U$24") (pin "D2") (pinfunction "D2_D2") (pintype "bidirectional"))
    )
    (net (code "104") (name "unconnected-(U$24-PadD3)") (class "Default")
      (node (ref "U$24") (pin "D3") (pinfunction "D3_D3") (pintype "bidirectional"))
    )
    (net (code "105") (name "unconnected-(U$24-PadD4)") (class "Default")
      (node (ref "U$24") (pin "D4") (pinfunction "D4_D4") (pintype "bidirectional"))
    )
    (net (code "106") (name "unconnected-(U$24-PadEN)") (class "Default")
      (node (ref "U$24") (pin "EN") (pinfunction "EN_EN") (pintype "bidirectional"))
    )
    (net (code "107") (name "unconnected-(U$24-PadRST)") (class "Default")
      (node (ref "U$24") (pin "RST") (pinfunction "RST_RST") (pintype "bidirectional"))
    )
    (net (code "108") (name "unconnected-(U$24-PadRSV)") (class "Default")
      (node (ref "U$24") (pin "RSV") (pinfunction "RSV_RSV") (pintype "bidirectional"))
    )
    (net (code "109") (name "unconnected-(U$24-PadRX)") (class "Default")
      (node (ref "U$24") (pin "RX") (pinfunction "RX_RX") (pintype "bidirectional"))
    )
    (net (code "110") (name "unconnected-(U$24-PadSD0)") (class "Default")
      (node (ref "U$24") (pin "SD0") (pinfunction "SD0_SD0") (pintype "bidirectional"))
    )
    (net (code "111") (name "unconnected-(U$24-PadSD1)") (class "Default")
      (node (ref "U$24") (pin "SD1") (pinfunction "SD1_SD1") (pintype "bidirectional"))
    )
    (net (code "112") (name "unconnected-(U$24-PadSD2)") (class "Default")
      (node (ref "U$24") (pin "SD2") (pinfunction "SD2_SD2") (pintype "bidirectional"))
    )
    (net (code "113") (name "unconnected-(U$24-PadSD3)") (class "Default")
      (node (ref "U$24") (pin "SD3") (pinfunction "SD3_SD3") (pintype "bidirectional"))
    )
    (net (code "114") (name "unconnected-(U$24-PadTX)") (class "Default")
      (node (ref "U$24") (pin "TX") (pinfunction "TX_TX") (pintype "bidirectional"))
    )
    (net (code "115") (name "unconnected-(U$24-RSV-PadRSV@1)") (class "Default")
      (node (ref "U$24") (pin "RSV@1") (pinfunction "RSV_RSV@1") (pintype "bidirectional"))
    )
    (net (code "116") (name "unconnected-(U1-A6-Pad9)") (class "Default")
      (node (ref "U1") (pin "9") (pinfunction "A6_9") (pintype "bidirectional"))
    )
    (net (code "117") (name "unconnected-(U1-A7-Pad10)") (class "Default")
      (node (ref "U1") (pin "10") (pinfunction "A7_10") (pintype "bidirectional"))
    )
    (net (code "118") (name "unconnected-(U1-B6-Pad15)") (class "Default")
      (node (ref "U1") (pin "15") (pinfunction "B6_15") (pintype "bidirectional"))
    )
    (net (code "119") (name "unconnected-(U1-B7-Pad14)") (class "Default")
      (node (ref "U1") (pin "14") (pinfunction "B7_14") (pintype "bidirectional"))
    )
  )
)
